# Controller.net
KiCad netlist of a schematic drawn in Altium Designer
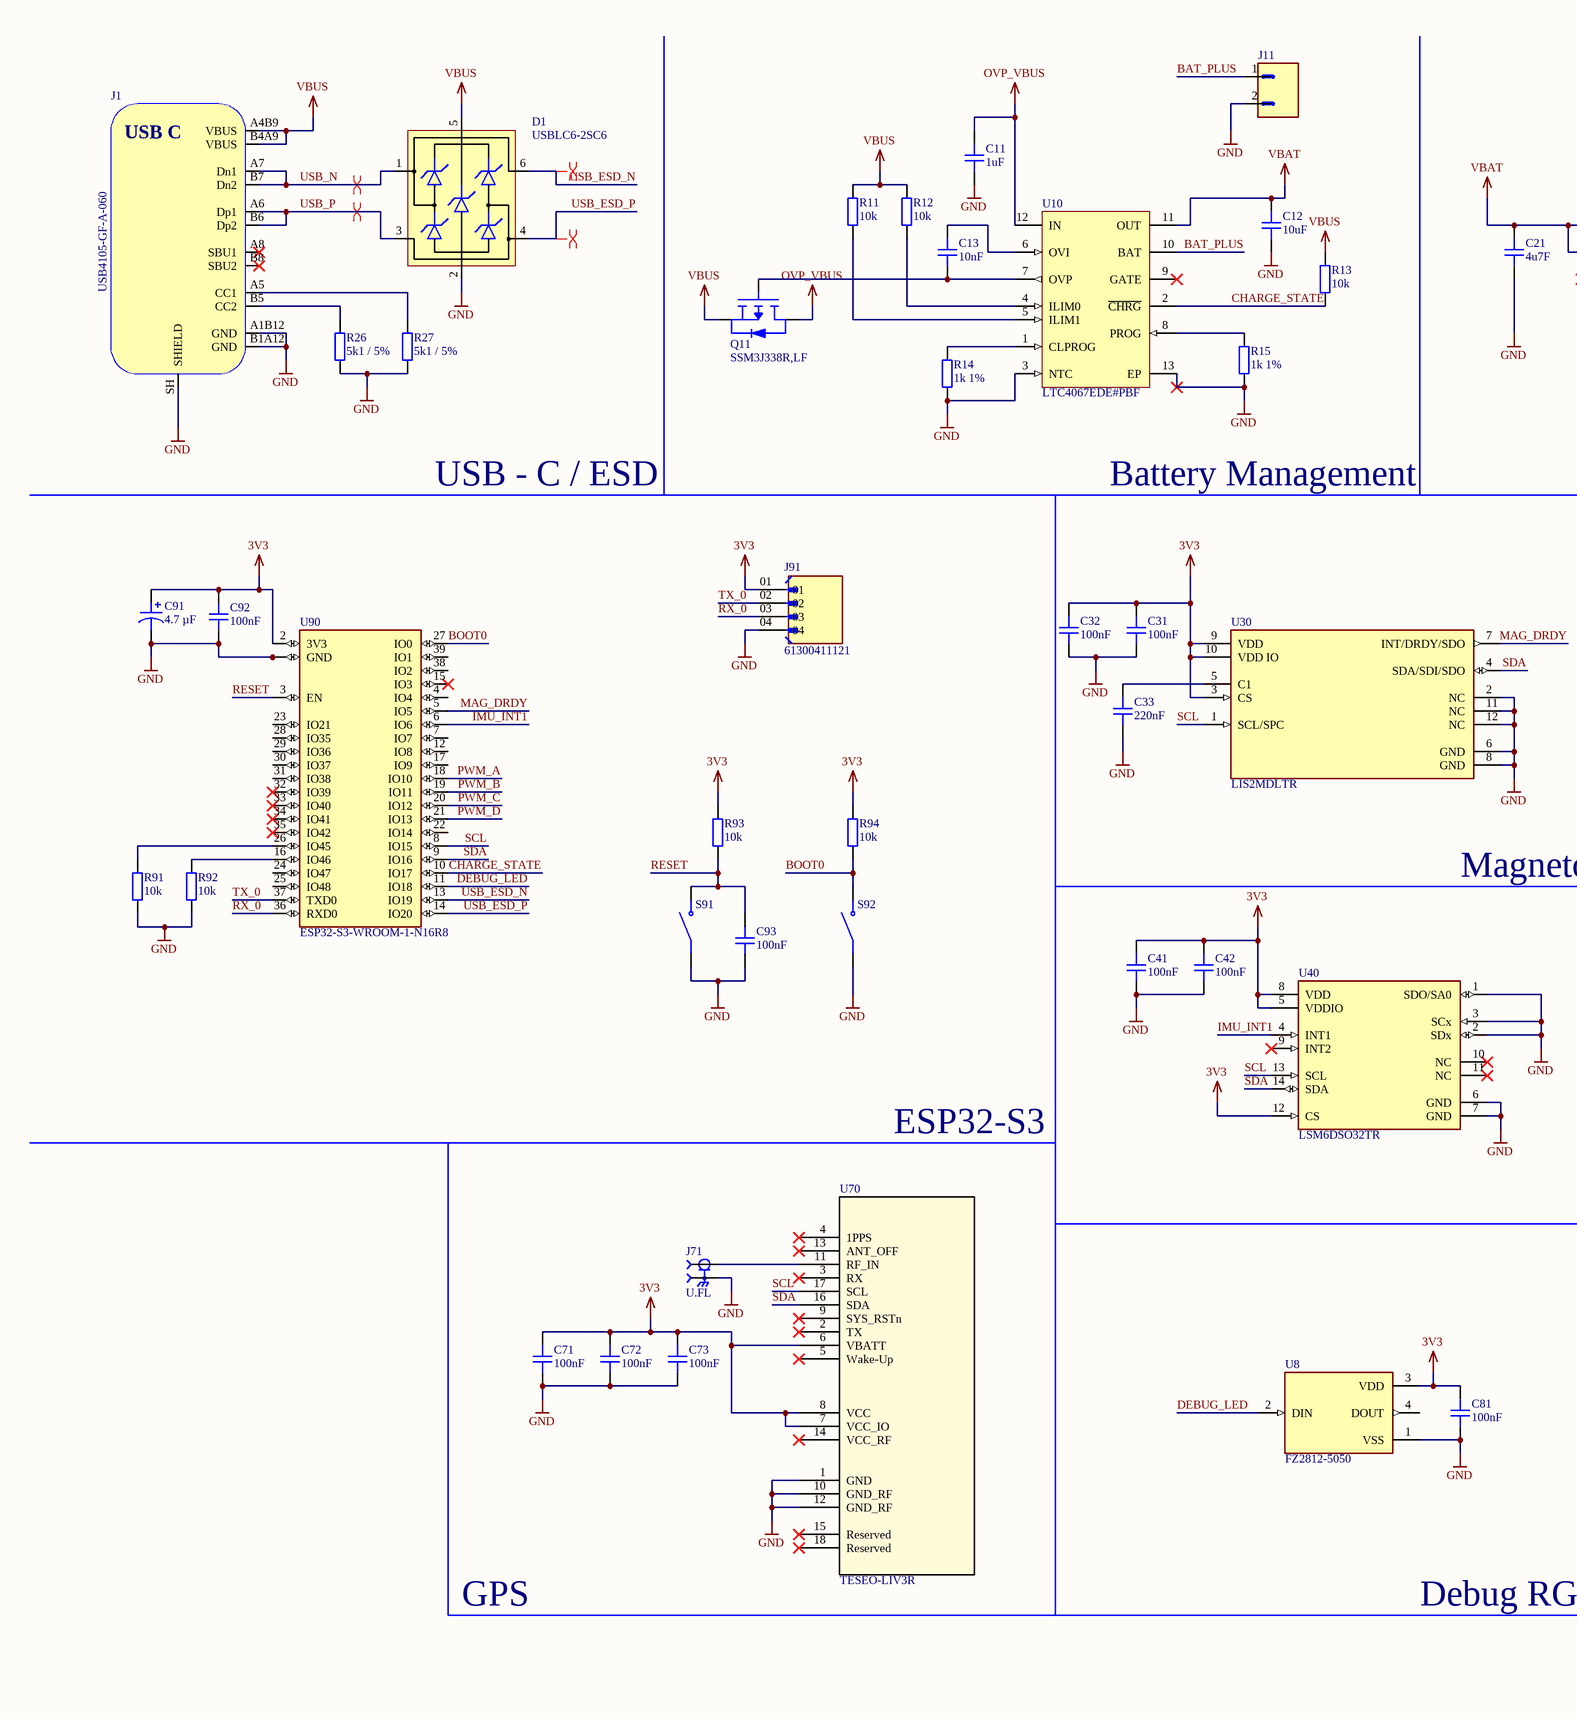
[diagram p0: Controller.SchDoc, left]
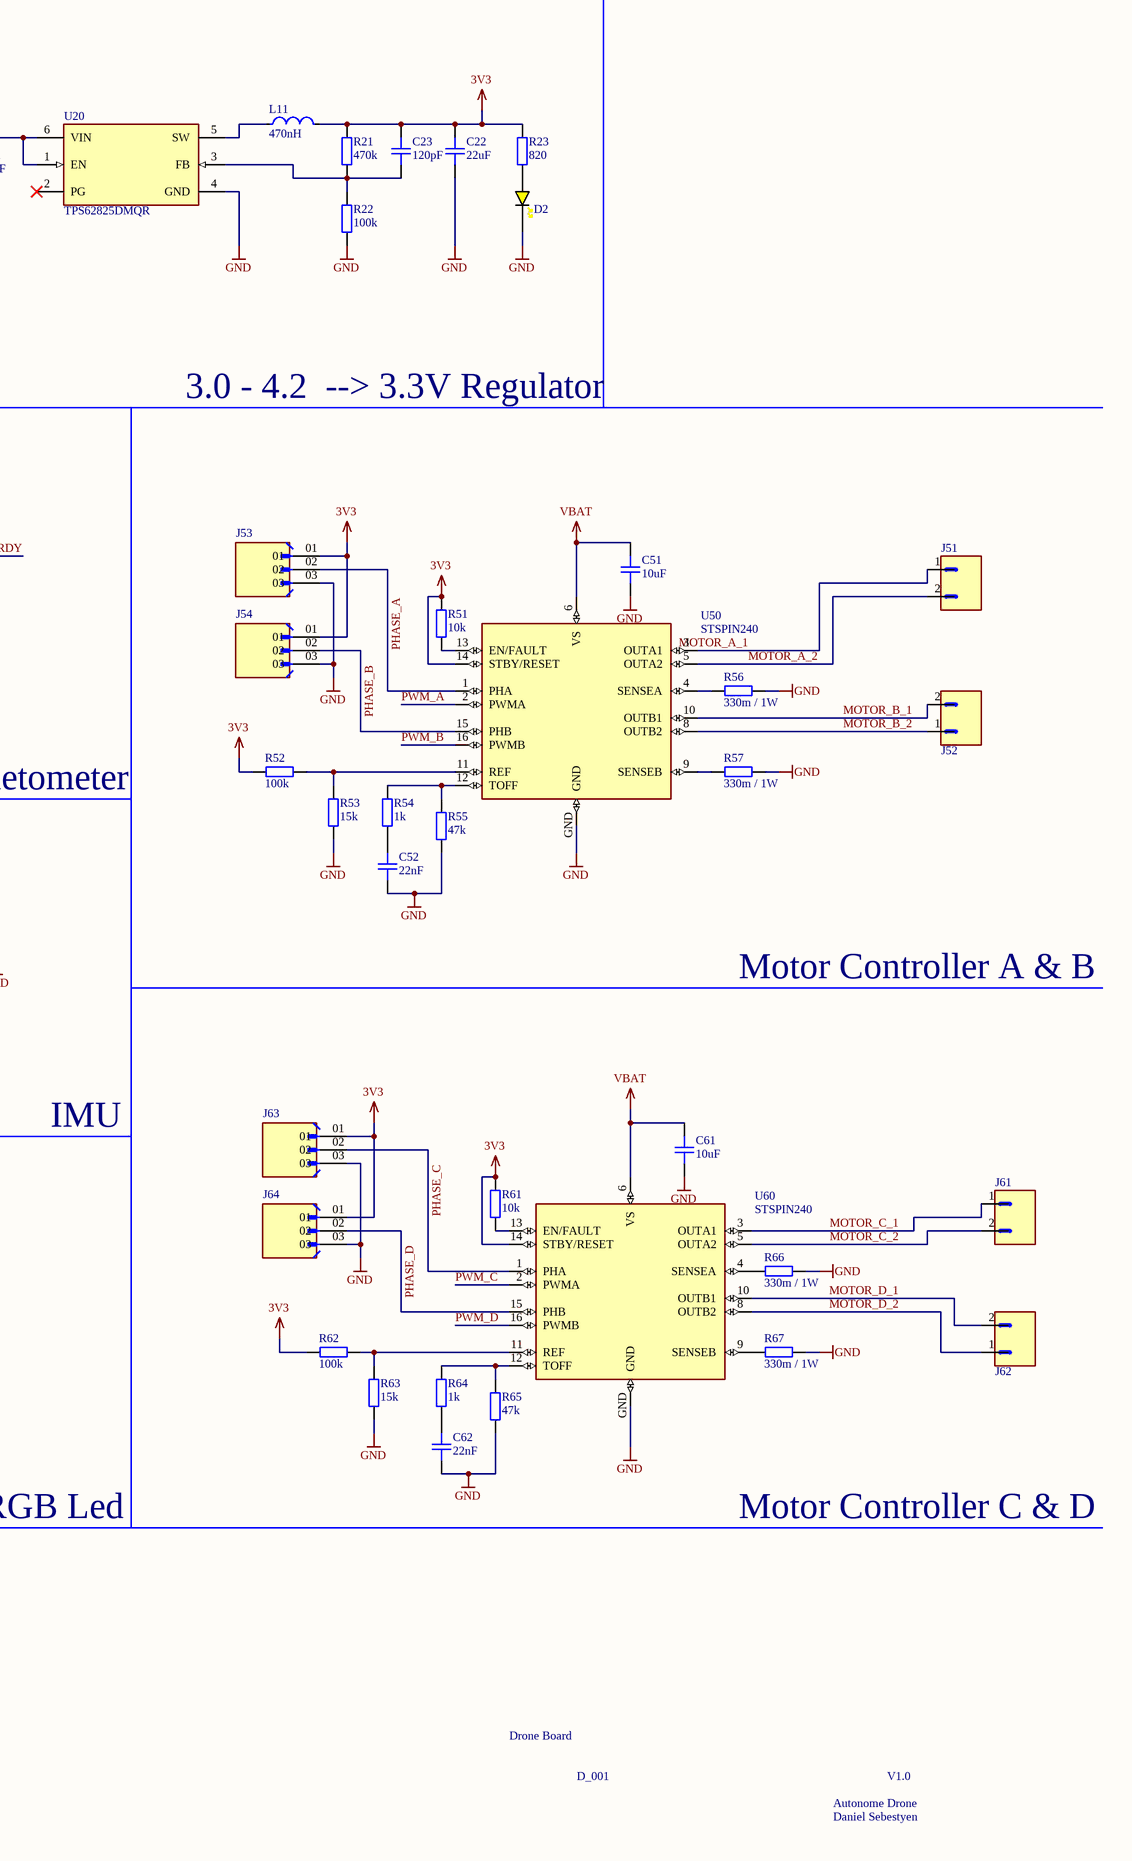
[diagram p1: Controller.SchDoc, right]

(export (version "E")
  (design (tool "Eeschema 10.0.6"))
  (components
    (comp (ref "C11")
      (value "1uF")
      (footprint "CAP_0201")
      (description "Capacitor SMD 0402")
      (libsource (lib "Schematic-Lib-PhilsLab") (part "CAP_0402"))
    )
    (comp (ref "C12")
      (value "10uF")
      (footprint "CAP_0201")
      (description "Capacitor SMD 0402")
      (libsource (lib "Schematic-Lib-PhilsLab") (part "CAP_0402"))
    )
    (comp (ref "C13")
      (value "10nF")
      (footprint "CAP_0201")
      (description "Capacitor SMD 0402")
      (libsource (lib "Schematic-Lib-PhilsLab") (part "CAP_0402"))
    )
    (comp (ref "C21")
      (value "4u7F")
      (footprint "CAP_0402")
      (description "Capacitor SMD 0603")
      (libsource (lib "Schematic-Lib-PhilsLab") (part "CAP_0603"))
    )
    (comp (ref "C22")
      (value "22uF")
      (footprint "CAP_0402")
      (description "Capacitor SMD 0603")
      (libsource (lib "Schematic-Lib-PhilsLab") (part "CAP_0603"))
    )
    (comp (ref "C23")
      (value "120pF")
      (footprint "CAP_0402")
      (description "Capacitor SMD 0603")
      (libsource (lib "Schematic-Lib-PhilsLab") (part "CAP_0603"))
    )
    (comp (ref "C31")
      (value "100nF")
      (footprint "CAP_0201")
      (description "Capacitor SMD 0402")
      (libsource (lib "Schematic-Lib-PhilsLab") (part "CAP_0402"))
    )
    (comp (ref "C32")
      (value "100nF")
      (footprint "CAP_0201")
      (description "Capacitor SMD 0402")
      (libsource (lib "Schematic-Lib-PhilsLab") (part "CAP_0402"))
    )
    (comp (ref "C33")
      (value "220nF")
      (footprint "CAP_0201")
      (description "Capacitor SMD 0402")
      (libsource (lib "Schematic-Lib-PhilsLab") (part "CAP_0402"))
    )
    (comp (ref "C41")
      (value "100nF")
      (footprint "CAP_0201")
      (description "Capacitor SMD 0402")
      (libsource (lib "Schematic-Lib-PhilsLab") (part "CAP_0402"))
    )
    (comp (ref "C42")
      (value "100nF")
      (footprint "CAP_0201")
      (description "Capacitor SMD 0402")
      (libsource (lib "Schematic-Lib-PhilsLab") (part "CAP_0402"))
    )
    (comp (ref "C51")
      (value "10uF")
      (footprint "CAP_0201")
      (description "Capacitor SMD 0402")
      (libsource (lib "Schematic-Lib-PhilsLab") (part "CAP_0402"))
    )
    (comp (ref "C52")
      (value "22nF")
      (footprint "CAP_0201")
      (description "Capacitor SMD 0402")
      (libsource (lib "Schematic-Lib-PhilsLab") (part "CAP_0402"))
    )
    (comp (ref "C61")
      (value "10uF")
      (footprint "CAP_0201")
      (description "Capacitor SMD 0402")
      (libsource (lib "Schematic-Lib-PhilsLab") (part "CAP_0402"))
    )
    (comp (ref "C62")
      (value "22nF")
      (footprint "CAP_0201")
      (description "Capacitor SMD 0402")
      (libsource (lib "Schematic-Lib-PhilsLab") (part "CAP_0402"))
    )
    (comp (ref "C71")
      (value "100nF")
      (footprint "CAP_0201")
      (description "Capacitor SMD 0402")
      (libsource (lib "Schematic-Lib-PhilsLab") (part "CAP_0402"))
    )
    (comp (ref "C72")
      (value "100nF")
      (footprint "CAP_0201")
      (description "Capacitor SMD 0402")
      (libsource (lib "Schematic-Lib-PhilsLab") (part "CAP_0402"))
    )
    (comp (ref "C73")
      (value "100nF")
      (footprint "CAP_0201")
      (description "Capacitor SMD 0402")
      (libsource (lib "Schematic-Lib-PhilsLab") (part "CAP_0402"))
    )
    (comp (ref "C81")
      (value "100nF")
      (footprint "CAP_0201")
      (description "Capacitor SMD 0402")
      (libsource (lib "Schematic-Lib-PhilsLab") (part "CAP_0402"))
    )
    (comp (ref "C91")
      (value "4.7 µF")
      (footprint "CAP ALSMD 4.3MM H5.4MM")
      (description "CAP ALUM 4.7UF 20% 16V SMD")
      (fields
        (field (name "PART NUMBER") "EEE-1CA4R7NR")
        (field (name "MANUFACTURER") "Panasonic Electronic Components")
      )
      (libsource (lib "Celestial Altium Library - altium_library") (part "Polarised Capacitor"))
    )
    (comp (ref "C92")
      (value "100nF")
      (footprint "CAP_0201")
      (description "Capacitor SMD 0402")
      (libsource (lib "Schematic-Lib-PhilsLab") (part "CAP_0402"))
    )
    (comp (ref "C93")
      (value "100nF")
      (footprint "CAP_0201")
      (description "Capacitor SMD 0402")
      (libsource (lib "Schematic-Lib-PhilsLab") (part "CAP_0402"))
    )
    (comp (ref "D1")
      (value "USBLC6-2SC6")
      (footprint "SOT-23-6")
      (description "Low-Capacitance ESD Protection USB")
      (fields (field (name "MANUFACTURER") "STMicroelectronics"))
      (libsource (lib "Schematic-Lib-PhilsLab") (part "USBLC6-2SC6"))
    )
    (comp (ref "D2")
      (value "1.8V")
      (footprint "LED_0402_YELLOW")
      (description "LED 0603 YELLOW SMD")
      (libsource (lib "Schematic-Lib-PhilsLab") (part "LED_0603_YELLOW"))
    )
    (comp (ref "J1")
      (value "USB4105-GF-A-060")
      (footprint "USB4105-GF-A-060")
      (description "USB Connector Type C SMT 12 Pin")
      (fields (field (name "MANUFACTURER") "GCT"))
      (libsource (lib "Schematic-Lib-PhilsLab") (part "USB4105-GF-A-060"))
    )
    (comp (ref "J11")
      (value "S2B-PH-SM4-TB(LF)(SN)")
      (footprint "S2B-PH-SM4-TB(LF)(SN)")
      (description "Connector Header Surface Mount, Right Angle 2 position 0.079 (2.00mm)")
      (fields (field (name "MF") "JST Sales"))
      (libsource (lib "S2B-PH-SM4-TB_LF__SN_") (part "S2B-PH-SM4-TB(LF)(SN)"))
    )
    (comp (ref "J51")
      (value "S2B-PH-SM4-TB(LF)(SN)")
      (footprint "S2B-PH-SM4-TB(LF)(SN)")
      (description "Connector Header Surface Mount, Right Angle 2 position 0.079 (2.00mm)")
      (fields (field (name "MF") "JST Sales"))
      (libsource (lib "S2B-PH-SM4-TB_LF__SN_") (part "S2B-PH-SM4-TB(LF)(SN)"))
    )
    (comp (ref "J52")
      (value "S2B-PH-SM4-TB(LF)(SN)")
      (footprint "S2B-PH-SM4-TB(LF)(SN)")
      (description "Connector Header Surface Mount, Right Angle 2 position 0.079 (2.00mm)")
      (fields (field (name "MF") "JST Sales"))
      (libsource (lib "") (part "S2B-PH-SM4-TB(LF)(SN)_1"))
    )
    (comp (ref "J53")
      (value "61300311121")
      (footprint "WURTH_61300311121")
      (description "Connector Header Through Hole 3 position 0.100 (2.54mm)")
      (fields (field (name "MF") "Wurth Electronics"))
      (libsource (lib "61300311121") (part "61300311121"))
    )
    (comp (ref "J54")
      (value "61300311121")
      (footprint "WURTH_61300311121")
      (description "Connector Header Through Hole 3 position 0.100 (2.54mm)")
      (fields (field (name "MF") "Wurth Electronics"))
      (libsource (lib "61300311121") (part "61300311121"))
    )
    (comp (ref "J61")
      (value "S2B-PH-SM4-TB(LF)(SN)")
      (footprint "S2B-PH-SM4-TB(LF)(SN)")
      (description "Connector Header Surface Mount, Right Angle 2 position 0.079 (2.00mm)")
      (fields (field (name "MF") "JST Sales"))
      (libsource (lib "S2B-PH-SM4-TB_LF__SN_") (part "S2B-PH-SM4-TB(LF)(SN)"))
    )
    (comp (ref "J62")
      (value "S2B-PH-SM4-TB(LF)(SN)")
      (footprint "S2B-PH-SM4-TB(LF)(SN)")
      (description "Connector Header Surface Mount, Right Angle 2 position 0.079 (2.00mm)")
      (fields (field (name "MF") "JST Sales"))
      (libsource (lib "") (part "S2B-PH-SM4-TB(LF)(SN)_1"))
    )
    (comp (ref "J63")
      (value "61300311121")
      (footprint "WURTH_61300311121")
      (description "Connector Header Through Hole 3 position 0.100 (2.54mm)")
      (fields (field (name "MF") "Wurth Electronics"))
      (libsource (lib "61300311121") (part "61300311121"))
    )
    (comp (ref "J64")
      (value "61300311121")
      (footprint "WURTH_61300311121")
      (description "Connector Header Through Hole 3 position 0.100 (2.54mm)")
      (fields (field (name "MF") "Wurth Electronics"))
      (libsource (lib "61300311121") (part "61300311121"))
    )
    (comp (ref "J71")
      (value "U.FL")
      (footprint "MOLEX_73412-0114")
      (description "Female Surface Mount Coaxial Socket, Solder Termination ¦ Molex Incorporated 73412-0114")
      (fields (field (name "MF") "Molex") (field (name "MP") "73412-0114"))
      (libsource (lib "73412-0114") (part "73412-0114"))
    )
    (comp (ref "J91")
      (value "61300411121")
      (footprint "WURTH_61300411121")
      (description "4 pins, 1 row, straight, gold plating")
      (fields (field (name "MF") "Wurth Electronics"))
      (libsource (lib "61300411121") (part "61300411121"))
    )
    (comp (ref "L11")
      (value "470nH")
      (footprint "FP-DFE201610C-MFG")
      (description "Shielded Wirewound Inductor 0.47uH 20% 3600mA 0.032Ω 0806 (2016)")
      (libsource (lib "Altium Content Vault") (part "725321dda6339637d4d059423bc1c3c"))
    )
    (comp (ref "Q11")
      (value "SSM3J338R,LF")
      (footprint "SSM3J338R,LF-SOT23-F")
      (description "MOSFET P-Channel Vds=12V Id=6A")
      (fields (field (name "MANUFACTURER PART NUMBER") "Toshiba"))
      (libsource (lib "Schematic-Lib-PhilsLab") (part "SSM3J338R,LF"))
    )
    (comp (ref "R11")
      (value "10k")
      (footprint "RES_0201")
      (description "Resistor SMD 0402")
      (libsource (lib "Schematic-Lib-PhilsLab") (part "RES_0402"))
    )
    (comp (ref "R12")
      (value "10k")
      (footprint "RES_0201")
      (description "Resistor SMD 0402")
      (libsource (lib "Schematic-Lib-PhilsLab") (part "RES_0402"))
    )
    (comp (ref "R13")
      (value "10k")
      (footprint "RES_0201")
      (description "Resistor SMD 0402")
      (libsource (lib "Schematic-Lib-PhilsLab") (part "RES_0402"))
    )
    (comp (ref "R14")
      (value "1k 1%")
      (footprint "RES_0201")
      (description "Resistor SMD 0402")
      (libsource (lib "Schematic-Lib-PhilsLab") (part "RES_0402"))
    )
    (comp (ref "R15")
      (value "1k 1%")
      (footprint "RES_0201")
      (description "Resistor SMD 0402")
      (libsource (lib "Schematic-Lib-PhilsLab") (part "RES_0402"))
    )
    (comp (ref "R21")
      (value "470k")
      (footprint "RES_0402")
      (description "Resistor SMD 0603")
      (libsource (lib "Schematic-Lib-PhilsLab") (part "RES_0603"))
    )
    (comp (ref "R22")
      (value "100k")
      (footprint "RES_0402")
      (description "Resistor SMD 0603")
      (libsource (lib "Schematic-Lib-PhilsLab") (part "RES_0603"))
    )
    (comp (ref "R23")
      (value "820")
      (footprint "RES_0402")
      (description "Resistor SMD 0603")
      (libsource (lib "Schematic-Lib-PhilsLab") (part "RES_0603"))
    )
    (comp (ref "R26")
      (value "5k1 / 5%")
      (footprint "RES_0201")
      (description "Resistor SMD 0402")
      (libsource (lib "Schematic-Lib-PhilsLab") (part "RES_0402"))
    )
    (comp (ref "R27")
      (value "5k1 / 5%")
      (footprint "RES_0201")
      (description "Resistor SMD 0402")
      (libsource (lib "Schematic-Lib-PhilsLab") (part "RES_0402"))
    )
    (comp (ref "R51")
      (value "10k")
      (footprint "RES_0201")
      (description "Resistor SMD 0402")
      (libsource (lib "Schematic-Lib-PhilsLab") (part "RES_0402"))
    )
    (comp (ref "R52")
      (value "100k")
      (footprint "RES_0201")
      (description "Resistor SMD 0402")
      (libsource (lib "Schematic-Lib-PhilsLab") (part "RES_0402"))
    )
    (comp (ref "R53")
      (value "15k")
      (footprint "RES_0201")
      (description "Resistor SMD 0402")
      (libsource (lib "Schematic-Lib-PhilsLab") (part "RES_0402"))
    )
    (comp (ref "R54")
      (value "1k")
      (footprint "RES_0201")
      (description "Resistor SMD 0402")
      (libsource (lib "Schematic-Lib-PhilsLab") (part "RES_0402"))
    )
    (comp (ref "R55")
      (value "47k")
      (footprint "RES_0201")
      (description "Resistor SMD 0402")
      (libsource (lib "Schematic-Lib-PhilsLab") (part "RES_0402"))
    )
    (comp (ref "R56")
      (value "330m / 1W")
      (footprint "RES_0201")
      (description "Resistor SMD 0402")
      (libsource (lib "Schematic-Lib-PhilsLab") (part "RES_0402"))
    )
    (comp (ref "R57")
      (value "330m / 1W")
      (footprint "RES_0201")
      (description "Resistor SMD 0402")
      (libsource (lib "Schematic-Lib-PhilsLab") (part "RES_0402"))
    )
    (comp (ref "R61")
      (value "10k")
      (footprint "RES_0201")
      (description "Resistor SMD 0402")
      (libsource (lib "Schematic-Lib-PhilsLab") (part "RES_0402"))
    )
    (comp (ref "R62")
      (value "100k")
      (footprint "RES_0201")
      (description "Resistor SMD 0402")
      (libsource (lib "Schematic-Lib-PhilsLab") (part "RES_0402"))
    )
    (comp (ref "R63")
      (value "15k")
      (footprint "RES_0201")
      (description "Resistor SMD 0402")
      (libsource (lib "Schematic-Lib-PhilsLab") (part "RES_0402"))
    )
    (comp (ref "R64")
      (value "1k")
      (footprint "RES_0201")
      (description "Resistor SMD 0402")
      (libsource (lib "Schematic-Lib-PhilsLab") (part "RES_0402"))
    )
    (comp (ref "R65")
      (value "47k")
      (footprint "RES_0201")
      (description "Resistor SMD 0402")
      (libsource (lib "Schematic-Lib-PhilsLab") (part "RES_0402"))
    )
    (comp (ref "R66")
      (value "330m / 1W")
      (footprint "RES_0201")
      (description "Resistor SMD 0402")
      (libsource (lib "Schematic-Lib-PhilsLab") (part "RES_0402"))
    )
    (comp (ref "R67")
      (value "330m / 1W")
      (footprint "RES_0201")
      (description "Resistor SMD 0402")
      (libsource (lib "Schematic-Lib-PhilsLab") (part "RES_0402"))
    )
    (comp (ref "R91")
      (value "10k")
      (footprint "RES_0201")
      (description "Resistor SMD 0402")
      (libsource (lib "Schematic-Lib-PhilsLab") (part "RES_0402"))
    )
    (comp (ref "R92")
      (value "10k")
      (footprint "RES_0201")
      (description "Resistor SMD 0402")
      (libsource (lib "Schematic-Lib-PhilsLab") (part "RES_0402"))
    )
    (comp (ref "R93")
      (value "10k")
      (footprint "RES_0201")
      (description "Resistor SMD 0402")
      (libsource (lib "Schematic-Lib-PhilsLab") (part "RES_0402"))
    )
    (comp (ref "R94")
      (value "10k")
      (footprint "RES_0201")
      (description "Resistor SMD 0402")
      (libsource (lib "Schematic-Lib-PhilsLab") (part "RES_0402"))
    )
    (comp (ref "S91")
      (value "PTS636_SM43J_SMTR_LFS")
      (footprint "SW_PTS636_SM43J_SMTR_LFS")
      (description "Tactile Switch SPST-NO Top Actuated Surface Mount")
      (fields (field (name "MF") "C&K") (field (name "MP") "PTS636 SM43J SMTR LFS"))
      (libsource (lib "PTS636_SM43J_SMTR_LFS") (part "PTS636_SM43J_SMTR_LFS"))
    )
    (comp (ref "S92")
      (value "PTS636_SM43J_SMTR_LFS")
      (footprint "SW_PTS636_SM43J_SMTR_LFS")
      (description "Tactile Switch SPST-NO Top Actuated Surface Mount")
      (fields (field (name "MF") "C&K") (field (name "MP") "PTS636 SM43J SMTR LFS"))
      (libsource (lib "PTS636_SM43J_SMTR_LFS") (part "PTS636_SM43J_SMTR_LFS"))
    )
    (comp (ref "U8")
      (value "FZ2812-5050")
      (footprint "LED_FZ2812-5050")
      (description "Addressable Lighting * 3 LED Discrete Serial Red, Green, Blue (RGB) 5.00mm L x 5.00mm W")
      (fields (field (name "MF") "Feztek"))
      (libsource (lib "FZ2812-5050") (part "FZ2812-5050"))
    )
    (comp (ref "U10")
      (value "LTC4067EDE#PBF")
      (footprint "LT-DE-UE-12_V")
      (fields (field (name "MANUFACTURER") "Linear Technology"))
      (libsource (lib "Altium Content Vault") (part "LT-LTC4067-DE-UE-12"))
    )
    (comp (ref "U20")
      (value "TPS62825DMQR")
      (footprint "FP-DMQ0006A-MFG")
      (description "IC REG BUCK ADJUSTABLE 2A 6VSON")
      (libsource (lib "Altium Content Vault") (part "e17fecc44d644f7e54801b5eb65f103"))
    )
    (comp (ref "U30")
      (value "LIS2MDLTR")
      (footprint "FP-LGA-12-DM00170568-MFG")
      (description "SENSOR MR I2C/SPI 12LGA")
      (fields
        (field (name "OCTOPART") "https://octopart.com/lis2mdltr-stmicroelectronics-81117311")
        (field (name "MANUFACTURER") "STMicroelectronics")
      )
      (libsource (lib "Altium Content Vault") (part "91637d6a6da3cb2d69b1e7726cd74d2"))
    )
    (comp (ref "U40")
      (value "LSM6DSO32TR")
      (footprint "FP-LGA-14L-DM00249496-MFG")
      (description "INEMO INERTIAL MODULE: 3D ACCELE")
      (libsource (lib "Altium Content Vault") (part "593856c316c551aebc7657d93cdb4f0"))
    )
    (comp (ref "U50")
      (value "STSPIN240")
      (footprint "VFQFPN_3X3X1MM")
      (description "Half Bridge (4) Driver DC Motors, General Purpose Power MOSFET 16-VFQFPN (3x3)")
      (fields (field (name "MF") "STMicroelectronics"))
      (libsource (lib "STSPIN240") (part "STSPIN240"))
    )
    (comp (ref "U60")
      (value "STSPIN240")
      (footprint "VFQFPN_3X3X1MM")
      (description "Half Bridge (4) Driver DC Motors, General Purpose Power MOSFET 16-VFQFPN (3x3)")
      (fields (field (name "MF") "STMicroelectronics"))
      (libsource (lib "STSPIN240") (part "STSPIN240"))
    )
    (comp (ref "U70")
      (value "TESEO-LIV3R")
      (footprint "ARRAY_LIV3R_STM")
      (description "No Description Available")
      (libsource (lib "TESEO-LIV3R") (part "TESEO-LIV3R"))
    )
    (comp (ref "U90")
      (value "ESP32-S3-WROOM-1-N16R8")
      (footprint "ESP32S3WROOM1N8R2")
      (description "Bluetooth, WiFi 802.11b/g/n, Bluetooth v5.0 Transceiver Module 2.4GHz PCB Trace Surface Mount")
      (fields (field (name "MF") "Espressif Systems"))
      (libsource (lib "ESP32-S3-WROOM-1-N16R8") (part "ESP32-S3-WROOM-1-N16R8"))
    )
  )
  (nets
    (net (code "1") (name "/BAT_PLUS") (class "Default")
      (node (ref "J11") (pin "1") (pinfunction "1_1") (pintype "passive"))
      (node (ref "U10") (pin "10") (pinfunction "BAT_10") (pintype "power_in"))
    )
    (net (code "2") (name "/BOOT0") (class "Default")
      (node (ref "R94") (pin "1") (pinfunction "1_1") (pintype "passive"))
      (node (ref "S92") (pin "2") (pinfunction "NO_2") (pintype "passive"))
      (node (ref "U90") (pin "27") (pinfunction "IO0_27") (pintype "bidirectional"))
    )
    (net (code "3") (name "/CHARGE_STATE") (class "Default")
      (node (ref "R13") (pin "1") (pinfunction "1_1") (pintype "passive"))
      (node (ref "U10") (pin "2") (pinfunction "~{CHRG}_2") (pintype "tri_state"))
      (node (ref "U90") (pin "10") (pinfunction "IO17_10") (pintype "bidirectional"))
    )
    (net (code "4") (name "/DEBUG_LED") (class "Default")
      (node (ref "U8") (pin "2") (pinfunction "DIN_2") (pintype "input"))
      (node (ref "U90") (pin "11") (pinfunction "IO18_11") (pintype "bidirectional"))
    )
    (net (code "5") (name "/IMU_INT1") (class "Default")
      (node (ref "U40") (pin "4") (pinfunction "INT1_4") (pintype "input"))
      (node (ref "U90") (pin "6") (pinfunction "IO6_6") (pintype "bidirectional"))
    )
    (net (code "6") (name "/MAG_DRDY") (class "Default")
      (node (ref "U30") (pin "7") (pinfunction "INT/DRDY/SDO_7") (pintype "output"))
      (node (ref "U90") (pin "5") (pinfunction "IO5_5") (pintype "bidirectional"))
    )
    (net (code "7") (name "/MOTOR_A_1") (class "Default")
      (node (ref "J51") (pin "1") (pinfunction "1_1") (pintype "passive"))
      (node (ref "U50") (pin "3") (pinfunction "OUTA1_3") (pintype "bidirectional"))
    )
    (net (code "8") (name "/MOTOR_A_2") (class "Default")
      (node (ref "J51") (pin "2") (pinfunction "2_2") (pintype "passive"))
      (node (ref "U50") (pin "5") (pinfunction "OUTA2_5") (pintype "bidirectional"))
    )
    (net (code "9") (name "/MOTOR_B_1") (class "Default")
      (node (ref "J52") (pin "2") (pinfunction "2_2") (pintype "passive"))
      (node (ref "U50") (pin "10") (pinfunction "OUTB1_10") (pintype "bidirectional"))
    )
    (net (code "10") (name "/MOTOR_B_2") (class "Default")
      (node (ref "J52") (pin "1") (pinfunction "1_1") (pintype "passive"))
      (node (ref "U50") (pin "8") (pinfunction "OUTB2_8") (pintype "bidirectional"))
    )
    (net (code "11") (name "/MOTOR_C_1") (class "Default")
      (node (ref "J61") (pin "1") (pinfunction "1_1") (pintype "passive"))
      (node (ref "U60") (pin "3") (pinfunction "OUTA1_3") (pintype "bidirectional"))
    )
    (net (code "12") (name "/MOTOR_C_2") (class "Default")
      (node (ref "J61") (pin "2") (pinfunction "2_2") (pintype "passive"))
      (node (ref "U60") (pin "5") (pinfunction "OUTA2_5") (pintype "bidirectional"))
    )
    (net (code "13") (name "/MOTOR_D_1") (class "Default")
      (node (ref "J62") (pin "2") (pinfunction "2_2") (pintype "passive"))
      (node (ref "U60") (pin "10") (pinfunction "OUTB1_10") (pintype "bidirectional"))
    )
    (net (code "14") (name "/MOTOR_D_2") (class "Default")
      (node (ref "J62") (pin "1") (pinfunction "1_1") (pintype "passive"))
      (node (ref "U60") (pin "8") (pinfunction "OUTB2_8") (pintype "bidirectional"))
    )
    (net (code "15") (name "/PHASE_A") (class "Default")
      (node (ref "J53") (pin "02") (pinfunction "02_02") (pintype "passive"))
      (node (ref "U50") (pin "1") (pinfunction "PHA_1") (pintype "bidirectional"))
    )
    (net (code "16") (name "/PHASE_B") (class "Default")
      (node (ref "J54") (pin "02") (pinfunction "02_02") (pintype "passive"))
      (node (ref "U50") (pin "15") (pinfunction "PHB_15") (pintype "bidirectional"))
    )
    (net (code "17") (name "/PHASE_C") (class "Default")
      (node (ref "J63") (pin "02") (pinfunction "02_02") (pintype "passive"))
      (node (ref "U60") (pin "1") (pinfunction "PHA_1") (pintype "bidirectional"))
    )
    (net (code "18") (name "/PHASE_D") (class "Default")
      (node (ref "J64") (pin "02") (pinfunction "02_02") (pintype "passive"))
      (node (ref "U60") (pin "15") (pinfunction "PHB_15") (pintype "bidirectional"))
    )
    (net (code "19") (name "/PWM_A") (class "Default")
      (node (ref "U50") (pin "2") (pinfunction "PWMA_2") (pintype "bidirectional"))
      (node (ref "U90") (pin "18") (pinfunction "IO10_18") (pintype "bidirectional"))
    )
    (net (code "20") (name "/PWM_B") (class "Default")
      (node (ref "U50") (pin "16") (pinfunction "PWMB_16") (pintype "bidirectional"))
      (node (ref "U90") (pin "19") (pinfunction "IO11_19") (pintype "bidirectional"))
    )
    (net (code "21") (name "/PWM_C") (class "Default")
      (node (ref "U60") (pin "2") (pinfunction "PWMA_2") (pintype "bidirectional"))
      (node (ref "U90") (pin "20") (pinfunction "IO12_20") (pintype "bidirectional"))
    )
    (net (code "22") (name "/PWM_D") (class "Default")
      (node (ref "U60") (pin "16") (pinfunction "PWMB_16") (pintype "bidirectional"))
      (node (ref "U90") (pin "21") (pinfunction "IO13_21") (pintype "bidirectional"))
    )
    (net (code "23") (name "/RESET") (class "Default")
      (node (ref "C93") (pin "2") (pinfunction "2_2") (pintype "passive"))
      (node (ref "R93") (pin "1") (pinfunction "1_1") (pintype "passive"))
      (node (ref "S91") (pin "2") (pinfunction "NO_2") (pintype "passive"))
      (node (ref "U90") (pin "3") (pinfunction "EN_3") (pintype "bidirectional"))
    )
    (net (code "24") (name "/RX_0") (class "Default")
      (node (ref "J91") (pin "03") (pinfunction "03_03") (pintype "passive"))
      (node (ref "U90") (pin "36") (pinfunction "RXD0_36") (pintype "bidirectional"))
    )
    (net (code "25") (name "/SCL") (class "Default")
      (node (ref "U30") (pin "1") (pinfunction "SCL/SPC_1") (pintype "input"))
      (node (ref "U40") (pin "13") (pinfunction "SCL_13") (pintype "input"))
      (node (ref "U70") (pin "17") (pinfunction "SCL_17") (pintype "passive"))
      (node (ref "U90") (pin "8") (pinfunction "IO15_8") (pintype "bidirectional"))
    )
    (net (code "26") (name "/SDA") (class "Default")
      (node (ref "U30") (pin "4") (pinfunction "SDA/SDI/SDO_4") (pintype "bidirectional"))
      (node (ref "U40") (pin "14") (pinfunction "SDA_14") (pintype "bidirectional"))
      (node (ref "U70") (pin "16") (pinfunction "SDA_16") (pintype "passive"))
      (node (ref "U90") (pin "9") (pinfunction "IO16_9") (pintype "bidirectional"))
    )
    (net (code "27") (name "/TX_0") (class "Default")
      (node (ref "J91") (pin "02") (pinfunction "02_02") (pintype "passive"))
      (node (ref "U90") (pin "37") (pinfunction "TXD0_37") (pintype "bidirectional"))
    )
    (net (code "28") (name "/USB_ESD_N") (class "Default")
      (node (ref "D1") (pin "6") (pinfunction "IO1_6") (pintype "bidirectional"))
      (node (ref "U90") (pin "13") (pinfunction "IO19_13") (pintype "bidirectional"))
    )
    (net (code "29") (name "/USB_ESD_P") (class "Default")
      (node (ref "D1") (pin "4") (pinfunction "IO2_4") (pintype "bidirectional"))
      (node (ref "U90") (pin "14") (pinfunction "IO20_14") (pintype "bidirectional"))
    )
    (net (code "30") (name "/USB_N") (class "Default")
      (node (ref "D1") (pin "1") (pinfunction "IO1_1") (pintype "bidirectional"))
      (node (ref "J1") (pin "A7") (pinfunction "Dn1_A7") (pintype "passive"))
      (node (ref "J1") (pin "B7") (pinfunction "Dn2_B7") (pintype "passive"))
    )
    (net (code "31") (name "/USB_P") (class "Default")
      (node (ref "D1") (pin "3") (pinfunction "IO2_3") (pintype "bidirectional"))
      (node (ref "J1") (pin "A6") (pinfunction "Dp1_A6") (pintype "passive"))
      (node (ref "J1") (pin "B6") (pinfunction "Dp2_B6") (pintype "passive"))
    )
    (net (code "32") (name "3V3") (class "Default")
      (node (ref "C22") (pin "2") (pinfunction "2_2") (pintype "passive"))
      (node (ref "C23") (pin "2") (pinfunction "2_2") (pintype "passive"))
      (node (ref "C31") (pin "2") (pinfunction "2_2") (pintype "passive"))
      (node (ref "C32") (pin "2") (pinfunction "2_2") (pintype "passive"))
      (node (ref "C41") (pin "2") (pinfunction "2_2") (pintype "passive"))
      (node (ref "C42") (pin "2") (pinfunction "2_2") (pintype "passive"))
      (node (ref "C71") (pin "2") (pinfunction "2_2") (pintype "passive"))
      (node (ref "C72") (pin "2") (pinfunction "2_2") (pintype "passive"))
      (node (ref "C73") (pin "2") (pinfunction "2_2") (pintype "passive"))
      (node (ref "C81") (pin "2") (pinfunction "2_2") (pintype "passive"))
      (node (ref "C91") (pin "1") (pinfunction "1_1") (pintype "passive"))
      (node (ref "C92") (pin "2") (pinfunction "2_2") (pintype "passive"))
      (node (ref "J53") (pin "01") (pinfunction "01_01") (pintype "passive"))
      (node (ref "J54") (pin "01") (pinfunction "01_01") (pintype "passive"))
      (node (ref "J63") (pin "01") (pinfunction "01_01") (pintype "passive"))
      (node (ref "J64") (pin "01") (pinfunction "01_01") (pintype "passive"))
      (node (ref "J91") (pin "01") (pinfunction "01_01") (pintype "passive"))
      (node (ref "L11") (pin "2") (pinfunction "2_2") (pintype "passive"))
      (node (ref "R21") (pin "2") (pinfunction "2_2") (pintype "passive"))
      (node (ref "R23") (pin "2") (pinfunction "2_2") (pintype "passive"))
      (node (ref "R51") (pin "1") (pinfunction "1_1") (pintype "passive"))
      (node (ref "R52") (pin "2") (pinfunction "2_2") (pintype "passive"))
      (node (ref "R61") (pin "1") (pinfunction "1_1") (pintype "passive"))
      (node (ref "R62") (pin "2") (pinfunction "2_2") (pintype "passive"))
      (node (ref "R93") (pin "2") (pinfunction "2_2") (pintype "passive"))
      (node (ref "R94") (pin "2") (pinfunction "2_2") (pintype "passive"))
      (node (ref "U30") (pin "10") (pinfunction "VDD_IO_10") (pintype "power_in"))
      (node (ref "U30") (pin "3") (pinfunction "CS_3") (pintype "input"))
      (node (ref "U30") (pin "9") (pinfunction "VDD_9") (pintype "power_in"))
      (node (ref "U40") (pin "12") (pinfunction "CS_12") (pintype "input"))
      (node (ref "U40") (pin "5") (pinfunction "VDDIO_5") (pintype "power_in"))
      (node (ref "U40") (pin "8") (pinfunction "VDD_8") (pintype "power_in"))
      (node (ref "U50") (pin "14") (pinfunction "STBY/RESET_14") (pintype "bidirectional"))
      (node (ref "U60") (pin "14") (pinfunction "STBY/RESET_14") (pintype "bidirectional"))
      (node (ref "U70") (pin "6") (pinfunction "VBATT_6") (pintype "passive"))
      (node (ref "U70") (pin "7") (pinfunction "VCC_IO_7") (pintype "power_in"))
      (node (ref "U70") (pin "8") (pinfunction "VCC_8") (pintype "power_in"))
      (node (ref "U8") (pin "3") (pinfunction "VDD_3") (pintype "power_in"))
      (node (ref "U90") (pin "2") (pinfunction "3V3_2") (pintype "bidirectional"))
    )
    (net (code "33") (name "GND") (class "Default")
      (node (ref "C11") (pin "1") (pinfunction "1_1") (pintype "passive"))
      (node (ref "C12") (pin "1") (pinfunction "1_1") (pintype "passive"))
      (node (ref "C21") (pin "1") (pinfunction "1_1") (pintype "passive"))
      (node (ref "C22") (pin "1") (pinfunction "1_1") (pintype "passive"))
      (node (ref "C31") (pin "1") (pinfunction "1_1") (pintype "passive"))
      (node (ref "C32") (pin "1") (pinfunction "1_1") (pintype "passive"))
      (node (ref "C33") (pin "1") (pinfunction "1_1") (pintype "passive"))
      (node (ref "C41") (pin "1") (pinfunction "1_1") (pintype "passive"))
      (node (ref "C42") (pin "1") (pinfunction "1_1") (pintype "passive"))
      (node (ref "C51") (pin "1") (pinfunction "1_1") (pintype "passive"))
      (node (ref "C52") (pin "1") (pinfunction "1_1") (pintype "passive"))
      (node (ref "C61") (pin "1") (pinfunction "1_1") (pintype "passive"))
      (node (ref "C62") (pin "1") (pinfunction "1_1") (pintype "passive"))
      (node (ref "C71") (pin "1") (pinfunction "1_1") (pintype "passive"))
      (node (ref "C72") (pin "1") (pinfunction "1_1") (pintype "passive"))
      (node (ref "C73") (pin "1") (pinfunction "1_1") (pintype "passive"))
      (node (ref "C81") (pin "1") (pinfunction "1_1") (pintype "passive"))
      (node (ref "C91") (pin "2") (pinfunction "2_2") (pintype "passive"))
      (node (ref "C92") (pin "1") (pinfunction "1_1") (pintype "passive"))
      (node (ref "C93") (pin "1") (pinfunction "1_1") (pintype "passive"))
      (node (ref "D1") (pin "2") (pinfunction "GND_2") (pintype "power_in"))
      (node (ref "D2") (pin "K") (pinfunction "K_K") (pintype "passive"))
      (node (ref "J1") (pin "A1B12") (pinfunction "GND_A1B12") (pintype "passive"))
      (node (ref "J1") (pin "B1A12") (pinfunction "GND_B1A12") (pintype "passive"))
      (node (ref "J1") (pin "SH") (pinfunction "SHIELD_SH") (pintype "passive"))
      (node (ref "J11") (pin "2") (pinfunction "2_2") (pintype "passive"))
      (node (ref "J53") (pin "03") (pinfunction "03_03") (pintype "passive"))
      (node (ref "J54") (pin "03") (pinfunction "03_03") (pintype "passive"))
      (node (ref "J63") (pin "03") (pinfunction "03_03") (pintype "passive"))
      (node (ref "J64") (pin "03") (pinfunction "03_03") (pintype "passive"))
      (node (ref "J71") (pin "GND") (pinfunction "GND_GND") (pintype "power_in"))
      (node (ref "J91") (pin "04") (pinfunction "04_04") (pintype "passive"))
      (node (ref "R14") (pin "1") (pinfunction "1_1") (pintype "passive"))
      (node (ref "R15") (pin "1") (pinfunction "1_1") (pintype "passive"))
      (node (ref "R22") (pin "1") (pinfunction "1_1") (pintype "passive"))
      (node (ref "R26") (pin "1") (pinfunction "1_1") (pintype "passive"))
      (node (ref "R27") (pin "1") (pinfunction "1_1") (pintype "passive"))
      (node (ref "R53") (pin "2") (pinfunction "2_2") (pintype "passive"))
      (node (ref "R55") (pin "2") (pinfunction "2_2") (pintype "passive"))
      (node (ref "R56") (pin "1") (pinfunction "1_1") (pintype "passive"))
      (node (ref "R57") (pin "1") (pinfunction "1_1") (pintype "passive"))
      (node (ref "R63") (pin "2") (pinfunction "2_2") (pintype "passive"))
      (node (ref "R65") (pin "2") (pinfunction "2_2") (pintype "passive"))
      (node (ref "R66") (pin "1") (pinfunction "1_1") (pintype "passive"))
      (node (ref "R67") (pin "1") (pinfunction "1_1") (pintype "passive"))
      (node (ref "R91") (pin "1") (pinfunction "1_1") (pintype "passive"))
      (node (ref "R92") (pin "1") (pinfunction "1_1") (pintype "passive"))
      (node (ref "S91") (pin "1") (pinfunction "COM_1") (pintype "passive"))
      (node (ref "S92") (pin "1") (pinfunction "COM_1") (pintype "passive"))
      (node (ref "U10") (pin "13") (pinfunction "EP_13") (pintype "power_in"))
      (node (ref "U10") (pin "3") (pinfunction "NTC_3") (pintype "input"))
      (node (ref "U20") (pin "4") (pinfunction "GND_4") (pintype "power_in"))
      (node (ref "U30") (pin "11") (pinfunction "NC_11") (pintype "passive"))
      (node (ref "U30") (pin "12") (pinfunction "NC_12") (pintype "passive"))
      (node (ref "U30") (pin "2") (pinfunction "NC_2") (pintype "passive"))
      (node (ref "U30") (pin "6") (pinfunction "GND_6") (pintype "power_in"))
      (node (ref "U30") (pin "8") (pinfunction "GND_8") (pintype "power_in"))
      (node (ref "U40") (pin "1") (pinfunction "SDO/SA0_1") (pintype "bidirectional"))
      (node (ref "U40") (pin "2") (pinfunction "SDx_2") (pintype "bidirectional"))
      (node (ref "U40") (pin "3") (pinfunction "SCx_3") (pintype "input"))
      (node (ref "U40") (pin "6") (pinfunction "GND_6") (pintype "power_in"))
      (node (ref "U40") (pin "7") (pinfunction "GND_7") (pintype "power_in"))
      (node (ref "U50") (pin "GND") (pinfunction "GND_GND") (pintype "bidirectional"))
      (node (ref "U60") (pin "GND") (pinfunction "GND_GND") (pintype "bidirectional"))
      (node (ref "U70") (pin "1") (pinfunction "GND_1") (pintype "power_in"))
      (node (ref "U70") (pin "10") (pinfunction "GND_RF_10") (pintype "power_in"))
      (node (ref "U70") (pin "12") (pinfunction "GND_RF_12") (pintype "power_in"))
      (node (ref "U8") (pin "1") (pinfunction "VSS_1") (pintype "power_in"))
      (node (ref "U90") (pin "1") (pinfunction "GND_1") (pintype "bidirectional"))
      (node (ref "U90") (pin "40") (pinfunction "GND_40") (pintype "bidirectional"))
      (node (ref "U90") (pin "41") (pinfunction "GND_41") (pintype "bidirectional"))
      (node (ref "U90") (pin "42") (pinfunction "GND_42") (pintype "bidirectional"))
      (node (ref "U90") (pin "43") (pinfunction "GND_43") (pintype "bidirectional"))
      (node (ref "U90") (pin "44") (pinfunction "GND_44") (pintype "bidirectional"))
      (node (ref "U90") (pin "45") (pinfunction "GND_45") (pintype "bidirectional"))
      (node (ref "U90") (pin "46") (pinfunction "GND_46") (pintype "bidirectional"))
      (node (ref "U90") (pin "47") (pinfunction "GND_47") (pintype "bidirectional"))
      (node (ref "U90") (pin "48") (pinfunction "GND_48") (pintype "bidirectional"))
      (node (ref "U90") (pin "49") (pinfunction "GND_49") (pintype "bidirectional"))
    )
    (net (code "34") (name "Net-(C52-Pad2)") (class "Default")
      (node (ref "C52") (pin "2") (pinfunction "2_2") (pintype "passive"))
      (node (ref "R54") (pin "2") (pinfunction "2_2") (pintype "passive"))
    )
    (net (code "35") (name "Net-(C62-Pad2)") (class "Default")
      (node (ref "C62") (pin "2") (pinfunction "2_2") (pintype "passive"))
      (node (ref "R64") (pin "2") (pinfunction "2_2") (pintype "passive"))
    )
    (net (code "36") (name "Net-(D2-PadA)") (class "Default")
      (node (ref "D2") (pin "A") (pinfunction "A_A") (pintype "passive"))
      (node (ref "R23") (pin "1") (pinfunction "1_1") (pintype "passive"))
    )
    (net (code "37") (name "Net-(J1-CC1)") (class "Default")
      (node (ref "J1") (pin "A5") (pinfunction "CC1_A5") (pintype "passive"))
      (node (ref "R27") (pin "2") (pinfunction "2_2") (pintype "passive"))
    )
    (net (code "38") (name "Net-(J1-CC2)") (class "Default")
      (node (ref "J1") (pin "B5") (pinfunction "CC2_B5") (pintype "passive"))
      (node (ref "R26") (pin "2") (pinfunction "2_2") (pintype "passive"))
    )
    (net (code "39") (name "Net-(J71-SIG)") (class "Default")
      (node (ref "J71") (pin "1") (pinfunction "SIG_1") (pintype "passive"))
      (node (ref "U70") (pin "11") (pinfunction "RF_IN_11") (pintype "passive"))
    )
    (net (code "40") (name "Net-(U10-CLPROG)") (class "Default")
      (node (ref "R14") (pin "2") (pinfunction "2_2") (pintype "passive"))
      (node (ref "U10") (pin "1") (pinfunction "CLPROG_1") (pintype "input"))
    )
    (net (code "41") (name "Net-(U10-ILIM0)") (class "Default")
      (node (ref "R12") (pin "1") (pinfunction "1_1") (pintype "passive"))
      (node (ref "U10") (pin "4") (pinfunction "ILIM0_4") (pintype "input"))
    )
    (net (code "42") (name "Net-(U10-ILIM1)") (class "Default")
      (node (ref "R11") (pin "1") (pinfunction "1_1") (pintype "passive"))
      (node (ref "U10") (pin "5") (pinfunction "ILIM1_5") (pintype "input"))
    )
    (net (code "43") (name "Net-(U10-OVI)") (class "Default")
      (node (ref "C13") (pin "2") (pinfunction "2_2") (pintype "passive"))
      (node (ref "U10") (pin "6") (pinfunction "OVI_6") (pintype "input"))
    )
    (net (code "44") (name "Net-(U10-OVP)") (class "Default")
      (node (ref "C13") (pin "1") (pinfunction "1_1") (pintype "passive"))
      (node (ref "Q11") (pin "G") (pinfunction "G_G") (pintype "passive"))
      (node (ref "U10") (pin "7") (pinfunction "OVP_7") (pintype "output"))
    )
    (net (code "45") (name "Net-(U10-PROG)") (class "Default")
      (node (ref "R15") (pin "2") (pinfunction "2_2") (pintype "passive"))
      (node (ref "U10") (pin "8") (pinfunction "PROG_8") (pintype "input"))
    )
    (net (code "46") (name "Net-(U20-FB)") (class "Default")
      (node (ref "C23") (pin "1") (pinfunction "1_1") (pintype "passive"))
      (node (ref "R21") (pin "1") (pinfunction "1_1") (pintype "passive"))
      (node (ref "R22") (pin "2") (pinfunction "2_2") (pintype "passive"))
      (node (ref "U20") (pin "3") (pinfunction "FB_3") (pintype "input"))
    )
    (net (code "47") (name "Net-(U20-SW)") (class "Default")
      (node (ref "L11") (pin "1") (pinfunction "1_1") (pintype "passive"))
      (node (ref "U20") (pin "5") (pinfunction "SW_5") (pintype "power_in"))
    )
    (net (code "48") (name "Net-(U30-C1)") (class "Default")
      (node (ref "C33") (pin "2") (pinfunction "2_2") (pintype "passive"))
      (node (ref "U30") (pin "5") (pinfunction "C1_5") (pintype "passive"))
    )
    (net (code "49") (name "Net-(U50-EN{slash}FAULT)") (class "Default")
      (node (ref "R51") (pin "2") (pinfunction "2_2") (pintype "passive"))
      (node (ref "U50") (pin "13") (pinfunction "EN/FAULT_13") (pintype "bidirectional"))
    )
    (net (code "50") (name "Net-(U50-REF)") (class "Default")
      (node (ref "R52") (pin "1") (pinfunction "1_1") (pintype "passive"))
      (node (ref "R53") (pin "1") (pinfunction "1_1") (pintype "passive"))
      (node (ref "U50") (pin "11") (pinfunction "REF_11") (pintype "bidirectional"))
    )
    (net (code "51") (name "Net-(U50-SENSEA)") (class "Default")
      (node (ref "R56") (pin "2") (pinfunction "2_2") (pintype "passive"))
      (node (ref "U50") (pin "4") (pinfunction "SENSEA_4") (pintype "bidirectional"))
    )
    (net (code "52") (name "Net-(U50-SENSEB)") (class "Default")
      (node (ref "R57") (pin "2") (pinfunction "2_2") (pintype "passive"))
      (node (ref "U50") (pin "9") (pinfunction "SENSEB_9") (pintype "bidirectional"))
    )
    (net (code "53") (name "Net-(U50-TOFF)") (class "Default")
      (node (ref "R54") (pin "1") (pinfunction "1_1") (pintype "passive"))
      (node (ref "R55") (pin "1") (pinfunction "1_1") (pintype "passive"))
      (node (ref "U50") (pin "12") (pinfunction "TOFF_12") (pintype "bidirectional"))
    )
    (net (code "54") (name "Net-(U60-EN{slash}FAULT)") (class "Default")
      (node (ref "R61") (pin "2") (pinfunction "2_2") (pintype "passive"))
      (node (ref "U60") (pin "13") (pinfunction "EN/FAULT_13") (pintype "bidirectional"))
    )
    (net (code "55") (name "Net-(U60-REF)") (class "Default")
      (node (ref "R62") (pin "1") (pinfunction "1_1") (pintype "passive"))
      (node (ref "R63") (pin "1") (pinfunction "1_1") (pintype "passive"))
      (node (ref "U60") (pin "11") (pinfunction "REF_11") (pintype "bidirectional"))
    )
    (net (code "56") (name "Net-(U60-SENSEA)") (class "Default")
      (node (ref "R66") (pin "2") (pinfunction "2_2") (pintype "passive"))
      (node (ref "U60") (pin "4") (pinfunction "SENSEA_4") (pintype "bidirectional"))
    )
    (net (code "57") (name "Net-(U60-SENSEB)") (class "Default")
      (node (ref "R67") (pin "2") (pinfunction "2_2") (pintype "passive"))
      (node (ref "U60") (pin "9") (pinfunction "SENSEB_9") (pintype "bidirectional"))
    )
    (net (code "58") (name "Net-(U60-TOFF)") (class "Default")
      (node (ref "R64") (pin "1") (pinfunction "1_1") (pintype "passive"))
      (node (ref "R65") (pin "1") (pinfunction "1_1") (pintype "passive"))
      (node (ref "U60") (pin "12") (pinfunction "TOFF_12") (pintype "bidirectional"))
    )
    (net (code "59") (name "Net-(U90-IO45)") (class "Default")
      (node (ref "R91") (pin "2") (pinfunction "2_2") (pintype "passive"))
      (node (ref "U90") (pin "26") (pinfunction "IO45_26") (pintype "bidirectional"))
    )
    (net (code "60") (name "Net-(U90-IO46)") (class "Default")
      (node (ref "R92") (pin "2") (pinfunction "2_2") (pintype "passive"))
      (node (ref "U90") (pin "16") (pinfunction "IO46_16") (pintype "bidirectional"))
    )
    (net (code "61") (name "OVP_VBUS") (class "Default")
      (node (ref "C11") (pin "2") (pinfunction "2_2") (pintype "passive"))
      (node (ref "Q11") (pin "D") (pinfunction "D_D") (pintype "passive"))
      (node (ref "U10") (pin "12") (pinfunction "IN_12") (pintype "power_in"))
    )
    (net (code "62") (name "VBAT") (class "Default")
      (node (ref "C12") (pin "2") (pinfunction "2_2") (pintype "passive"))
      (node (ref "C21") (pin "2") (pinfunction "2_2") (pintype "passive"))
      (node (ref "C51") (pin "2") (pinfunction "2_2") (pintype "passive"))
      (node (ref "C61") (pin "2") (pinfunction "2_2") (pintype "passive"))
      (node (ref "U10") (pin "11") (pinfunction "OUT_11") (pintype "power_in"))
      (node (ref "U20") (pin "1") (pinfunction "EN_1") (pintype "input"))
      (node (ref "U20") (pin "6") (pinfunction "VIN_6") (pintype "power_in"))
      (node (ref "U50") (pin "6") (pinfunction "VS_6") (pintype "bidirectional"))
      (node (ref "U60") (pin "6") (pinfunction "VS_6") (pintype "bidirectional"))
    )
    (net (code "63") (name "VBUS") (class "Default")
      (node (ref "D1") (pin "5") (pinfunction "VBUS_5") (pintype "power_in"))
      (node (ref "J1") (pin "A4B9") (pinfunction "VBUS_A4B9") (pintype "passive"))
      (node (ref "J1") (pin "B4A9") (pinfunction "VBUS_B4A9") (pintype "passive"))
      (node (ref "Q11") (pin "S") (pinfunction "S_S") (pintype "passive"))
      (node (ref "R11") (pin "2") (pinfunction "2_2") (pintype "passive"))
      (node (ref "R12") (pin "2") (pinfunction "2_2") (pintype "passive"))
      (node (ref "R13") (pin "2") (pinfunction "2_2") (pintype "passive"))
    )
    (net (code "64") (name "unconnected-(J1-SBU1-PadA8)") (class "Default")
      (node (ref "J1") (pin "A8") (pinfunction "SBU1_A8") (pintype "passive+no_connect"))
    )
    (net (code "65") (name "unconnected-(J1-SBU2-PadB8)") (class "Default")
      (node (ref "J1") (pin "B8") (pinfunction "SBU2_B8") (pintype "passive+no_connect"))
    )
    (net (code "66") (name "unconnected-(U8-DOUT-Pad4)") (class "Default")
      (node (ref "U8") (pin "4") (pinfunction "DOUT_4") (pintype "output"))
    )
    (net (code "67") (name "unconnected-(U10-GATE-Pad9)") (class "Default")
      (node (ref "U10") (pin "9") (pinfunction "GATE_9") (pintype "tri_state+no_connect"))
    )
    (net (code "68") (name "unconnected-(U20-PG-Pad2)") (class "Default")
      (node (ref "U20") (pin "2") (pinfunction "PG_2") (pintype "open_collector+no_connect"))
    )
    (net (code "69") (name "unconnected-(U40-INT2-Pad9)") (class "Default")
      (node (ref "U40") (pin "9") (pinfunction "INT2_9") (pintype "input+no_connect"))
    )
    (net (code "70") (name "unconnected-(U40-NC-Pad10)") (class "Default")
      (node (ref "U40") (pin "10") (pinfunction "NC_10") (pintype "passive+no_connect"))
    )
    (net (code "71") (name "unconnected-(U40-NC-Pad11)") (class "Default")
      (node (ref "U40") (pin "11") (pinfunction "NC_11") (pintype "passive+no_connect"))
    )
    (net (code "72") (name "unconnected-(U70-1PPS-Pad4)") (class "Default")
      (node (ref "U70") (pin "4") (pinfunction "1PPS_4") (pintype "passive+no_connect"))
    )
    (net (code "73") (name "unconnected-(U70-ANT_OFF-Pad13)") (class "Default")
      (node (ref "U70") (pin "13") (pinfunction "ANT_OFF_13") (pintype "passive+no_connect"))
    )
    (net (code "74") (name "unconnected-(U70-RX-Pad3)") (class "Default")
      (node (ref "U70") (pin "3") (pinfunction "RX_3") (pintype "passive+no_connect"))
    )
    (net (code "75") (name "unconnected-(U70-Reserved-Pad15)") (class "Default")
      (node (ref "U70") (pin "15") (pinfunction "Reserved_15") (pintype "passive+no_connect"))
    )
    (net (code "76") (name "unconnected-(U70-Reserved-Pad18)") (class "Default")
      (node (ref "U70") (pin "18") (pinfunction "Reserved_18") (pintype "passive+no_connect"))
    )
    (net (code "77") (name "unconnected-(U70-SYS_RSTn-Pad9)") (class "Default")
      (node (ref "U70") (pin "9") (pinfunction "SYS_RSTn_9") (pintype "passive+no_connect"))
    )
    (net (code "78") (name "unconnected-(U70-TX-Pad2)") (class "Default")
      (node (ref "U70") (pin "2") (pinfunction "TX_2") (pintype "passive+no_connect"))
    )
    (net (code "79") (name "unconnected-(U70-VCC_RF-Pad14)") (class "Default")
      (node (ref "U70") (pin "14") (pinfunction "VCC_RF_14") (pintype "power_in+no_connect"))
    )
    (net (code "80") (name "unconnected-(U70-Wake-Up-Pad5)") (class "Default")
      (node (ref "U70") (pin "5") (pinfunction "Wake-Up_5") (pintype "passive+no_connect"))
    )
    (net (code "81") (name "unconnected-(U90-IO1-Pad39)") (class "Default")
      (node (ref "U90") (pin "39") (pinfunction "IO1_39") (pintype "bidirectional"))
    )
    (net (code "82") (name "unconnected-(U90-IO2-Pad38)") (class "Default")
      (node (ref "U90") (pin "38") (pinfunction "IO2_38") (pintype "bidirectional"))
    )
    (net (code "83") (name "unconnected-(U90-IO3-Pad15)") (class "Default")
      (node (ref "U90") (pin "15") (pinfunction "IO3_15") (pintype "bidirectional+no_connect"))
    )
    (net (code "84") (name "unconnected-(U90-IO4-Pad4)") (class "Default")
      (node (ref "U90") (pin "4") (pinfunction "IO4_4") (pintype "bidirectional"))
    )
    (net (code "85") (name "unconnected-(U90-IO7-Pad7)") (class "Default")
      (node (ref "U90") (pin "7") (pinfunction "IO7_7") (pintype "bidirectional"))
    )
    (net (code "86") (name "unconnected-(U90-IO8-Pad12)") (class "Default")
      (node (ref "U90") (pin "12") (pinfunction "IO8_12") (pintype "bidirectional"))
    )
    (net (code "87") (name "unconnected-(U90-IO9-Pad17)") (class "Default")
      (node (ref "U90") (pin "17") (pinfunction "IO9_17") (pintype "bidirectional"))
    )
    (net (code "88") (name "unconnected-(U90-IO14-Pad22)") (class "Default")
      (node (ref "U90") (pin "22") (pinfunction "IO14_22") (pintype "bidirectional"))
    )
    (net (code "89") (name "unconnected-(U90-IO21-Pad23)") (class "Default")
      (node (ref "U90") (pin "23") (pinfunction "IO21_23") (pintype "bidirectional"))
    )
    (net (code "90") (name "unconnected-(U90-IO35-Pad28)") (class "Default")
      (node (ref "U90") (pin "28") (pinfunction "IO35_28") (pintype "bidirectional"))
    )
    (net (code "91") (name "unconnected-(U90-IO36-Pad29)") (class "Default")
      (node (ref "U90") (pin "29") (pinfunction "IO36_29") (pintype "bidirectional"))
    )
    (net (code "92") (name "unconnected-(U90-IO37-Pad30)") (class "Default")
      (node (ref "U90") (pin "30") (pinfunction "IO37_30") (pintype "bidirectional"))
    )
    (net (code "93") (name "unconnected-(U90-IO38-Pad31)") (class "Default")
      (node (ref "U90") (pin "31") (pinfunction "IO38_31") (pintype "bidirectional"))
    )
    (net (code "94") (name "unconnected-(U90-IO39-Pad32)") (class "Default")
      (node (ref "U90") (pin "32") (pinfunction "IO39_32") (pintype "bidirectional+no_connect"))
    )
    (net (code "95") (name "unconnected-(U90-IO40-Pad33)") (class "Default")
      (node (ref "U90") (pin "33") (pinfunction "IO40_33") (pintype "bidirectional+no_connect"))
    )
    (net (code "96") (name "unconnected-(U90-IO41-Pad34)") (class "Default")
      (node (ref "U90") (pin "34") (pinfunction "IO41_34") (pintype "bidirectional+no_connect"))
    )
    (net (code "97") (name "unconnected-(U90-IO42-Pad35)") (class "Default")
      (node (ref "U90") (pin "35") (pinfunction "IO42_35") (pintype "bidirectional+no_connect"))
    )
    (net (code "98") (name "unconnected-(U90-IO47-Pad24)") (class "Default")
      (node (ref "U90") (pin "24") (pinfunction "IO47_24") (pintype "bidirectional"))
    )
    (net (code "99") (name "unconnected-(U90-IO48-Pad25)") (class "Default")
      (node (ref "U90") (pin "25") (pinfunction "IO48_25") (pintype "bidirectional"))
    )
  )
)
